# pinout-eagle-schematic.net
KiCad netlist of a schematic drawn in EAGLE
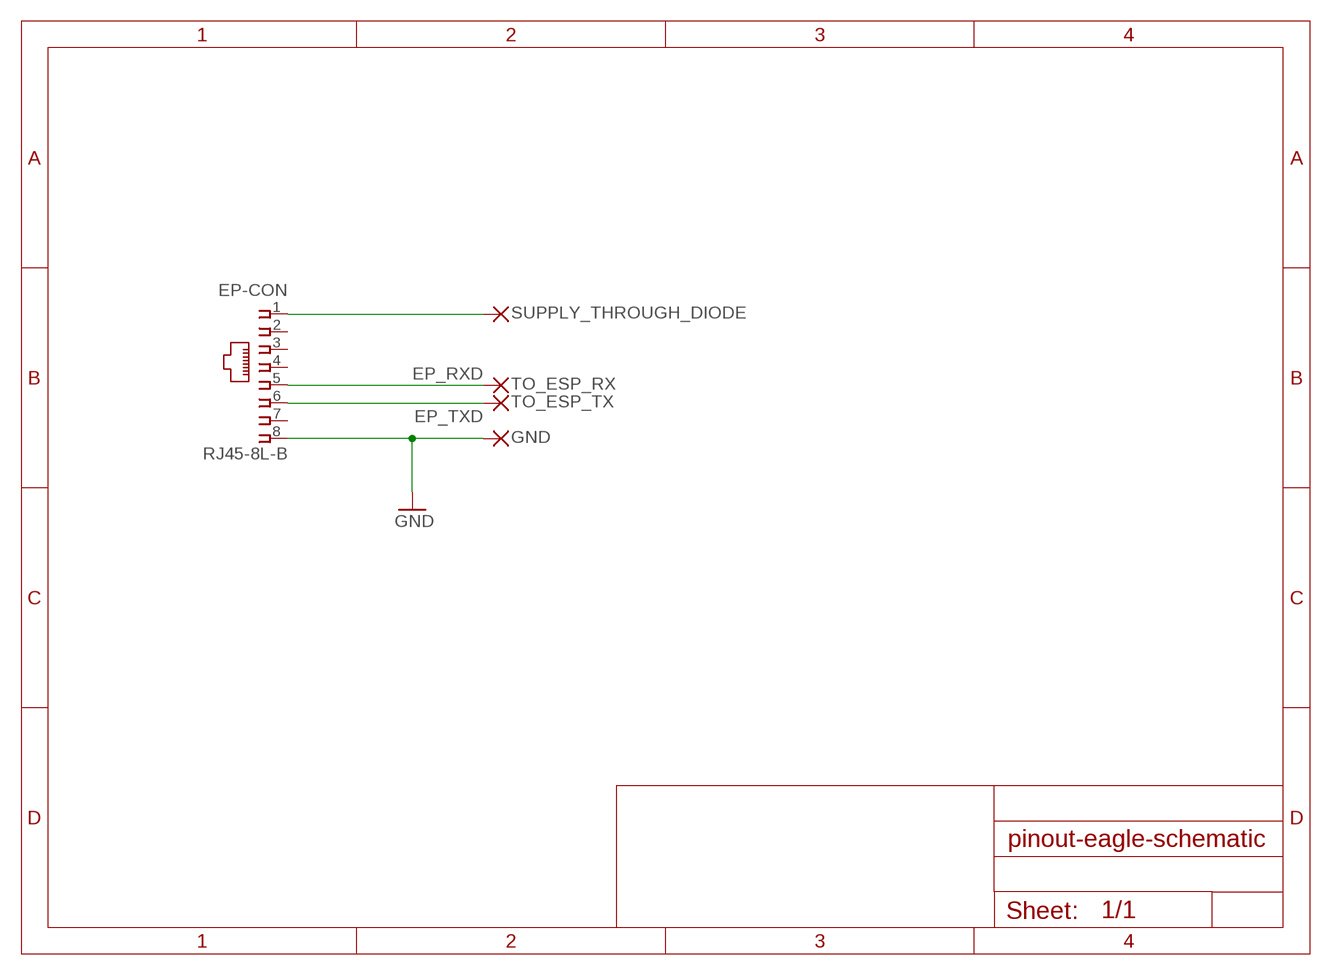
[diagram p0: schematic, sheet 1]

(export (version "E")
  (design (tool "Eeschema 10.0.6"))
  (components
    (comp (ref "EP-CON")
      (value "RJ45-8L-B")
      (footprint "eagle-import:RJ45-NO-SHIELD")
      (fields (field (name "MF") "TYCO ELECTRONICS"))
      (libsource (lib "eagle-import") (part "RJ45-8L-B"))
    )
    (comp (ref "GND")
      (value "SMD2")
      (footprint "eagle-import:SMD1,27-2,54")
      (libsource (lib "eagle-import") (part "SMD2"))
    )
    (comp (ref "SUPPLY_THROUGH_DIODE")
      (value "SMD2")
      (footprint "eagle-import:SMD1,27-2,54")
      (libsource (lib "eagle-import") (part "SMD2"))
    )
    (comp (ref "TO_ESP_RX")
      (value "SMD2")
      (footprint "eagle-import:SMD1,27-2,54")
      (libsource (lib "eagle-import") (part "SMD2"))
    )
    (comp (ref "TO_ESP_TX")
      (value "SMD2")
      (footprint "eagle-import:SMD1,27-2,54")
      (libsource (lib "eagle-import") (part "SMD2"))
    )
  )
  (nets
    (net (code "1") (name "/EP_RXD") (class "Default")
      (node (ref "EP-CON") (pin "5") (pinfunction "5_5") (pintype "passive"))
      (node (ref "TO_ESP_RX") (pin "1") (pinfunction "P_1") (pintype "passive"))
    )
    (net (code "2") (name "/EP_TXD") (class "Default")
      (node (ref "EP-CON") (pin "6") (pinfunction "6_6") (pintype "passive"))
      (node (ref "TO_ESP_TX") (pin "1") (pinfunction "P_1") (pintype "passive"))
    )
    (net (code "3") (name "GND") (class "Default")
      (node (ref "EP-CON") (pin "8") (pinfunction "8_8") (pintype "passive"))
      (node (ref "GND") (pin "1") (pinfunction "P_1") (pintype "passive"))
    )
    (net (code "4") (name "Net-(SUPPLY_THROUGH_DIODE-P)") (class "Default")
      (node (ref "EP-CON") (pin "1") (pinfunction "1_1") (pintype "passive"))
      (node (ref "SUPPLY_THROUGH_DIODE") (pin "1") (pinfunction "P_1") (pintype "passive"))
    )
    (net (code "5") (name "unconnected-(EP-CON-Pad2)") (class "Default")
      (node (ref "EP-CON") (pin "2") (pinfunction "2_2") (pintype "passive"))
    )
    (net (code "6") (name "unconnected-(EP-CON-Pad3)") (class "Default")
      (node (ref "EP-CON") (pin "3") (pinfunction "3_3") (pintype "passive"))
    )
    (net (code "7") (name "unconnected-(EP-CON-Pad4)") (class "Default")
      (node (ref "EP-CON") (pin "4") (pinfunction "4_4") (pintype "passive"))
    )
    (net (code "8") (name "unconnected-(EP-CON-Pad7)") (class "Default")
      (node (ref "EP-CON") (pin "7") (pinfunction "7_7") (pintype "passive"))
    )
  )
)
